# wifi-controller-x4-rev-A.net
KiCad netlist of a schematic drawn in EAGLE
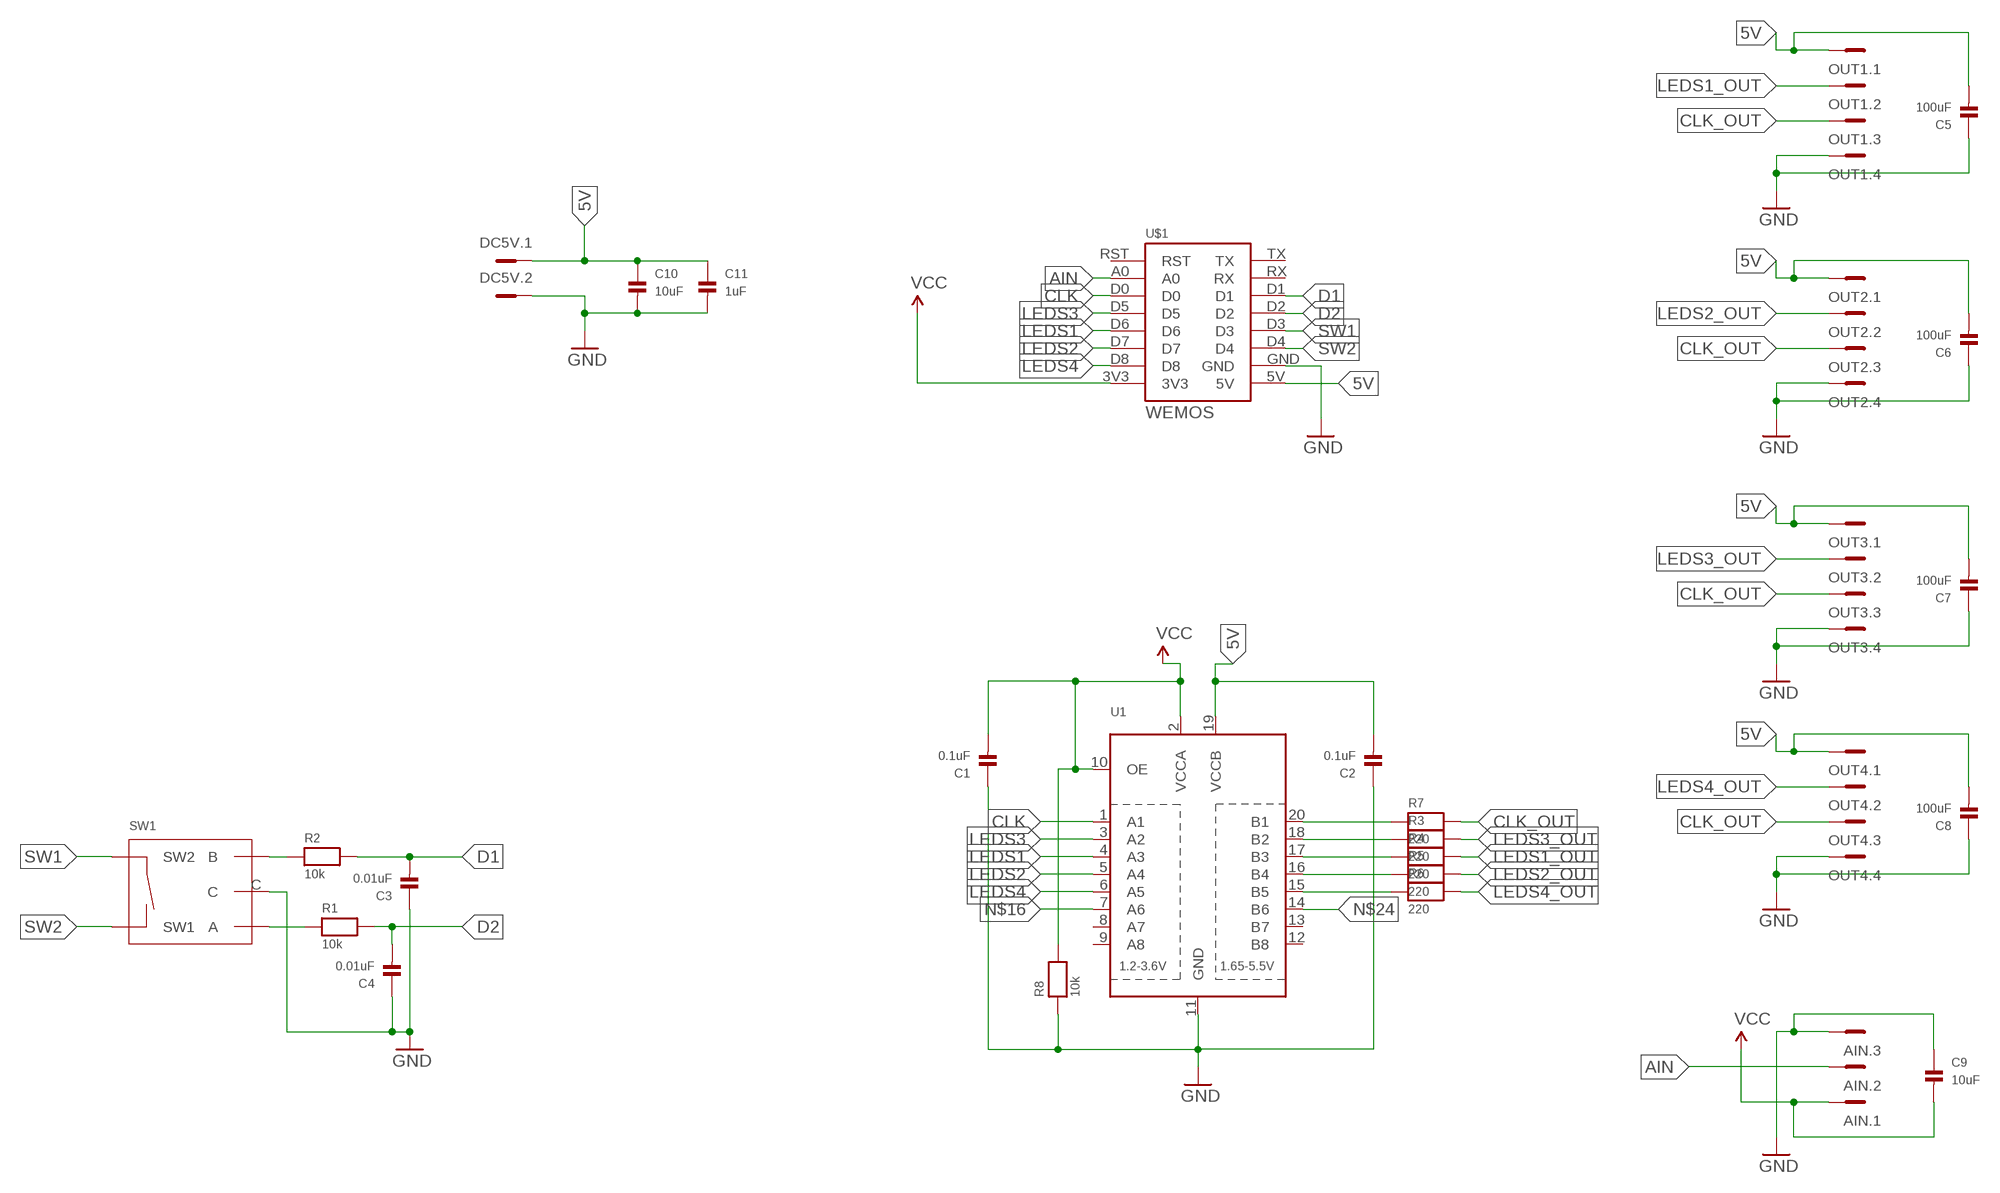
[diagram p0: schematic, sheet 1]

(export (version "E")
  (design (tool "Eeschema 10.0.6"))
  (components
    (comp (ref "AIN")
      (value "MC3")
      (footprint "eagle-import:MC3")
      (libsource (lib "eagle-import") (part "MC3"))
    )
    (comp (ref "C1")
      (value "0.1uF")
      (footprint "eagle-import:0603")
      (libsource (lib "eagle-import") (part "CAP_CERAMIC0603"))
    )
    (comp (ref "C2")
      (value "0.1uF")
      (footprint "eagle-import:0603")
      (libsource (lib "eagle-import") (part "CAP_CERAMIC0603"))
    )
    (comp (ref "C3")
      (value "0.01uF")
      (footprint "eagle-import:0603")
      (libsource (lib "eagle-import") (part "CAP_CERAMIC0603"))
    )
    (comp (ref "C4")
      (value "0.01uF")
      (footprint "eagle-import:0603")
      (libsource (lib "eagle-import") (part "CAP_CERAMIC0603"))
    )
    (comp (ref "C5")
      (value "100uF")
      (footprint "eagle-import:1206")
      (libsource (lib "eagle-import") (part "CAP_CERAMIC1206"))
    )
    (comp (ref "C6")
      (value "100uF")
      (footprint "eagle-import:1206")
      (libsource (lib "eagle-import") (part "CAP_CERAMIC1206"))
    )
    (comp (ref "C7")
      (value "100uF")
      (footprint "eagle-import:1206")
      (libsource (lib "eagle-import") (part "CAP_CERAMIC1206"))
    )
    (comp (ref "C8")
      (value "100uF")
      (footprint "eagle-import:1206")
      (libsource (lib "eagle-import") (part "CAP_CERAMIC1206"))
    )
    (comp (ref "C9")
      (value "10uF")
      (footprint "eagle-import:0603")
      (libsource (lib "eagle-import") (part "CAP_CERAMIC0603"))
    )
    (comp (ref "C10")
      (value "10uF")
      (footprint "eagle-import:0603")
      (libsource (lib "eagle-import") (part "CAP_CERAMIC0603"))
    )
    (comp (ref "C11")
      (value "1uF")
      (footprint "eagle-import:0603")
      (libsource (lib "eagle-import") (part "CAP_CERAMIC0603"))
    )
    (comp (ref "DC5V")
      (value "MC2")
      (footprint "eagle-import:MC2")
      (libsource (lib "eagle-import") (part "MC2"))
    )
    (comp (ref "OUT1")
      (value "MC4")
      (footprint "eagle-import:MC4")
      (libsource (lib "eagle-import") (part "MC4"))
    )
    (comp (ref "OUT2")
      (value "MC4")
      (footprint "eagle-import:MC4")
      (libsource (lib "eagle-import") (part "MC4"))
    )
    (comp (ref "OUT3")
      (value "MC4")
      (footprint "eagle-import:MC4")
      (libsource (lib "eagle-import") (part "MC4"))
    )
    (comp (ref "OUT4")
      (value "MC4")
      (footprint "eagle-import:MC4")
      (libsource (lib "eagle-import") (part "MC4"))
    )
    (comp (ref "R1")
      (value "10k")
      (footprint "eagle-import:0603")
      (libsource (lib "eagle-import") (part "RESISTOR0603"))
    )
    (comp (ref "R2")
      (value "10k")
      (footprint "eagle-import:0603")
      (libsource (lib "eagle-import") (part "RESISTOR0603"))
    )
    (comp (ref "R3")
      (value "220")
      (footprint "eagle-import:0603")
      (libsource (lib "eagle-import") (part "RESISTOR0603"))
    )
    (comp (ref "R4")
      (value "220")
      (footprint "eagle-import:0603")
      (libsource (lib "eagle-import") (part "RESISTOR0603"))
    )
    (comp (ref "R5")
      (value "220")
      (footprint "eagle-import:0603")
      (libsource (lib "eagle-import") (part "RESISTOR0603"))
    )
    (comp (ref "R6")
      (value "220")
      (footprint "eagle-import:0603")
      (libsource (lib "eagle-import") (part "RESISTOR0603"))
    )
    (comp (ref "R7")
      (value "220")
      (footprint "eagle-import:0603")
      (libsource (lib "eagle-import") (part "RESISTOR0603"))
    )
    (comp (ref "R8")
      (value "10k")
      (footprint "eagle-import:0603")
      (libsource (lib "eagle-import") (part "RESISTOR0603"))
    )
    (comp (ref "SW1")
      (value "ROTARY-ENCODER-BOURNS-PEC11S")
      (footprint "eagle-import:PEC11S")
      (libsource (lib "eagle-import") (part "ROTARY-ENCODER-BOURNS-PEC11S"))
    )
    (comp (ref "U$1")
      (value "WEMOS")
      (footprint "eagle-import:WEMOS")
      (libsource (lib "eagle-import") (part "WEMOS"))
    )
    (comp (ref "U1")
      (value "TXB0108PWR")
      (footprint "eagle-import:TSSOP20")
      (libsource (lib "eagle-import") (part "TXB0108PWR"))
    )
  )
  (nets
    (net (code "1") (name "5V") (class "Default")
      (node (ref "C10") (pin "1") (pinfunction "P$1_1") (pintype "passive"))
      (node (ref "C11") (pin "1") (pinfunction "P$1_1") (pintype "passive"))
      (node (ref "C2") (pin "2") (pinfunction "P$2_2") (pintype "passive"))
      (node (ref "C5") (pin "2") (pinfunction "P$2_2") (pintype "passive"))
      (node (ref "C6") (pin "2") (pinfunction "P$2_2") (pintype "passive"))
      (node (ref "C7") (pin "2") (pinfunction "P$2_2") (pintype "passive"))
      (node (ref "C8") (pin "2") (pinfunction "P$2_2") (pintype "passive"))
      (node (ref "DC5V") (pin "1") (pinfunction "SK_1") (pintype "passive"))
      (node (ref "OUT1") (pin "1") (pinfunction "SK_1") (pintype "passive"))
      (node (ref "OUT2") (pin "1") (pinfunction "SK_1") (pintype "passive"))
      (node (ref "OUT3") (pin "1") (pinfunction "SK_1") (pintype "passive"))
      (node (ref "OUT4") (pin "1") (pinfunction "SK_1") (pintype "passive"))
      (node (ref "U$1") (pin "5V") (pinfunction "5V_5V") (pintype "bidirectional"))
      (node (ref "U1") (pin "19") (pinfunction "VCCB_19") (pintype "bidirectional"))
    )
    (net (code "2") (name "AIN") (class "Default")
      (node (ref "AIN") (pin "2") (pinfunction "SK_2") (pintype "passive"))
      (node (ref "U$1") (pin "A0") (pinfunction "A0_A0") (pintype "bidirectional"))
    )
    (net (code "3") (name "CLK") (class "Default")
      (node (ref "U$1") (pin "D0") (pinfunction "D0_D0") (pintype "bidirectional"))
      (node (ref "U1") (pin "1") (pinfunction "A1_1") (pintype "bidirectional"))
    )
    (net (code "4") (name "CLK_OUT") (class "Default")
      (node (ref "OUT1") (pin "3") (pinfunction "SK_3") (pintype "passive"))
      (node (ref "OUT2") (pin "3") (pinfunction "SK_3") (pintype "passive"))
      (node (ref "OUT3") (pin "3") (pinfunction "SK_3") (pintype "passive"))
      (node (ref "OUT4") (pin "3") (pinfunction "SK_3") (pintype "passive"))
      (node (ref "R7") (pin "2") (pinfunction "2_2") (pintype "passive"))
    )
    (net (code "5") (name "D1") (class "Default")
      (node (ref "C3") (pin "2") (pinfunction "P$2_2") (pintype "passive"))
      (node (ref "R2") (pin "2") (pinfunction "2_2") (pintype "passive"))
      (node (ref "U$1") (pin "D1") (pinfunction "D1_D1") (pintype "bidirectional"))
    )
    (net (code "6") (name "D2") (class "Default")
      (node (ref "C4") (pin "2") (pinfunction "P$2_2") (pintype "passive"))
      (node (ref "R1") (pin "2") (pinfunction "2_2") (pintype "passive"))
      (node (ref "U$1") (pin "D2") (pinfunction "D2_D2") (pintype "bidirectional"))
    )
    (net (code "7") (name "GND") (class "Default")
      (node (ref "AIN") (pin "3") (pinfunction "SK_3") (pintype "passive"))
      (node (ref "C1") (pin "1") (pinfunction "P$1_1") (pintype "passive"))
      (node (ref "C10") (pin "2") (pinfunction "P$2_2") (pintype "passive"))
      (node (ref "C11") (pin "2") (pinfunction "P$2_2") (pintype "passive"))
      (node (ref "C2") (pin "1") (pinfunction "P$1_1") (pintype "passive"))
      (node (ref "C3") (pin "1") (pinfunction "P$1_1") (pintype "passive"))
      (node (ref "C4") (pin "1") (pinfunction "P$1_1") (pintype "passive"))
      (node (ref "C5") (pin "1") (pinfunction "P$1_1") (pintype "passive"))
      (node (ref "C6") (pin "1") (pinfunction "P$1_1") (pintype "passive"))
      (node (ref "C7") (pin "1") (pinfunction "P$1_1") (pintype "passive"))
      (node (ref "C8") (pin "1") (pinfunction "P$1_1") (pintype "passive"))
      (node (ref "C9") (pin "1") (pinfunction "P$1_1") (pintype "passive"))
      (node (ref "DC5V") (pin "2") (pinfunction "SK_2") (pintype "passive"))
      (node (ref "OUT1") (pin "4") (pinfunction "SK_4") (pintype "passive"))
      (node (ref "OUT2") (pin "4") (pinfunction "SK_4") (pintype "passive"))
      (node (ref "OUT3") (pin "4") (pinfunction "SK_4") (pintype "passive"))
      (node (ref "OUT4") (pin "4") (pinfunction "SK_4") (pintype "passive"))
      (node (ref "R8") (pin "1") (pinfunction "1_1") (pintype "passive"))
      (node (ref "SW1") (pin "C") (pinfunction "C_C") (pintype "input"))
      (node (ref "U$1") (pin "GND") (pinfunction "GND_GND") (pintype "bidirectional"))
      (node (ref "U1") (pin "11") (pinfunction "GND_11") (pintype "bidirectional"))
    )
    (net (code "8") (name "LEDS1") (class "Default")
      (node (ref "U$1") (pin "D6") (pinfunction "D6_D6") (pintype "bidirectional"))
      (node (ref "U1") (pin "4") (pinfunction "A3_4") (pintype "bidirectional"))
    )
    (net (code "9") (name "LEDS1_OUT") (class "Default")
      (node (ref "OUT1") (pin "2") (pinfunction "SK_2") (pintype "passive"))
      (node (ref "R4") (pin "2") (pinfunction "2_2") (pintype "passive"))
    )
    (net (code "10") (name "LEDS2") (class "Default")
      (node (ref "U$1") (pin "D7") (pinfunction "D7_D7") (pintype "bidirectional"))
      (node (ref "U1") (pin "5") (pinfunction "A4_5") (pintype "bidirectional"))
    )
    (net (code "11") (name "LEDS2_OUT") (class "Default")
      (node (ref "OUT2") (pin "2") (pinfunction "SK_2") (pintype "passive"))
      (node (ref "R5") (pin "2") (pinfunction "2_2") (pintype "passive"))
    )
    (net (code "12") (name "LEDS3") (class "Default")
      (node (ref "U$1") (pin "D5") (pinfunction "D5_D5") (pintype "bidirectional"))
      (node (ref "U1") (pin "3") (pinfunction "A2_3") (pintype "bidirectional"))
    )
    (net (code "13") (name "LEDS3_OUT") (class "Default")
      (node (ref "OUT3") (pin "2") (pinfunction "SK_2") (pintype "passive"))
      (node (ref "R3") (pin "2") (pinfunction "2_2") (pintype "passive"))
    )
    (net (code "14") (name "LEDS4") (class "Default")
      (node (ref "U$1") (pin "D8") (pinfunction "D8_D8") (pintype "bidirectional"))
      (node (ref "U1") (pin "6") (pinfunction "A5_6") (pintype "bidirectional"))
    )
    (net (code "15") (name "LEDS4_OUT") (class "Default")
      (node (ref "OUT4") (pin "2") (pinfunction "SK_2") (pintype "passive"))
      (node (ref "R6") (pin "2") (pinfunction "2_2") (pintype "passive"))
    )
    (net (code "16") (name "N$16") (class "Default")
      (node (ref "U1") (pin "7") (pinfunction "A6_7") (pintype "bidirectional"))
    )
    (net (code "17") (name "N$24") (class "Default")
      (node (ref "U1") (pin "14") (pinfunction "B6_14") (pintype "bidirectional"))
    )
    (net (code "18") (name "Net-(R1-Pad1)") (class "Default")
      (node (ref "R1") (pin "1") (pinfunction "1_1") (pintype "passive"))
      (node (ref "SW1") (pin "A") (pinfunction "A_A") (pintype "output"))
    )
    (net (code "19") (name "Net-(R2-Pad1)") (class "Default")
      (node (ref "R2") (pin "1") (pinfunction "1_1") (pintype "passive"))
      (node (ref "SW1") (pin "B") (pinfunction "B_B") (pintype "output"))
    )
    (net (code "20") (name "Net-(U1-B1)") (class "Default")
      (node (ref "R7") (pin "1") (pinfunction "1_1") (pintype "passive"))
      (node (ref "U1") (pin "20") (pinfunction "B1_20") (pintype "bidirectional"))
    )
    (net (code "21") (name "Net-(U1-B2)") (class "Default")
      (node (ref "R3") (pin "1") (pinfunction "1_1") (pintype "passive"))
      (node (ref "U1") (pin "18") (pinfunction "B2_18") (pintype "bidirectional"))
    )
    (net (code "22") (name "Net-(U1-B3)") (class "Default")
      (node (ref "R4") (pin "1") (pinfunction "1_1") (pintype "passive"))
      (node (ref "U1") (pin "17") (pinfunction "B3_17") (pintype "bidirectional"))
    )
    (net (code "23") (name "Net-(U1-B4)") (class "Default")
      (node (ref "R5") (pin "1") (pinfunction "1_1") (pintype "passive"))
      (node (ref "U1") (pin "16") (pinfunction "B4_16") (pintype "bidirectional"))
    )
    (net (code "24") (name "Net-(U1-B5)") (class "Default")
      (node (ref "R6") (pin "1") (pinfunction "1_1") (pintype "passive"))
      (node (ref "U1") (pin "15") (pinfunction "B5_15") (pintype "bidirectional"))
    )
    (net (code "25") (name "SW1") (class "Default")
      (node (ref "SW1") (pin "E") (pinfunction "SW2_E") (pintype "bidirectional"))
      (node (ref "U$1") (pin "D3") (pinfunction "D3_D3") (pintype "bidirectional"))
    )
    (net (code "26") (name "SW2") (class "Default")
      (node (ref "SW1") (pin "D") (pinfunction "SW1_D") (pintype "bidirectional"))
      (node (ref "U$1") (pin "D4") (pinfunction "D4_D4") (pintype "bidirectional"))
    )
    (net (code "27") (name "VCC") (class "Default")
      (node (ref "AIN") (pin "1") (pinfunction "SK_1") (pintype "passive"))
      (node (ref "C1") (pin "2") (pinfunction "P$2_2") (pintype "passive"))
      (node (ref "C9") (pin "2") (pinfunction "P$2_2") (pintype "passive"))
      (node (ref "R8") (pin "2") (pinfunction "2_2") (pintype "passive"))
      (node (ref "U$1") (pin "3V3") (pinfunction "3V3_3V3") (pintype "bidirectional"))
      (node (ref "U1") (pin "10") (pinfunction "OE_10") (pintype "bidirectional"))
      (node (ref "U1") (pin "2") (pinfunction "VCCA_2") (pintype "bidirectional"))
    )
    (net (code "28") (name "unconnected-(U$1-PadRST)") (class "Default")
      (node (ref "U$1") (pin "RST") (pinfunction "RST_RST") (pintype "bidirectional"))
    )
    (net (code "29") (name "unconnected-(U$1-PadRX)") (class "Default")
      (node (ref "U$1") (pin "RX") (pinfunction "RX_RX") (pintype "bidirectional"))
    )
    (net (code "30") (name "unconnected-(U$1-PadTX)") (class "Default")
      (node (ref "U$1") (pin "TX") (pinfunction "TX_TX") (pintype "bidirectional"))
    )
    (net (code "31") (name "unconnected-(U1-A7-Pad8)") (class "Default")
      (node (ref "U1") (pin "8") (pinfunction "A7_8") (pintype "bidirectional"))
    )
    (net (code "32") (name "unconnected-(U1-A8-Pad9)") (class "Default")
      (node (ref "U1") (pin "9") (pinfunction "A8_9") (pintype "bidirectional"))
    )
    (net (code "33") (name "unconnected-(U1-B7-Pad13)") (class "Default")
      (node (ref "U1") (pin "13") (pinfunction "B7_13") (pintype "bidirectional"))
    )
    (net (code "34") (name "unconnected-(U1-B8-Pad12)") (class "Default")
      (node (ref "U1") (pin "12") (pinfunction "B8_12") (pintype "bidirectional"))
    )
  )
)
